# OrangePi_Zero2.net
KiCad netlist of a schematic drawn in Altium Designer
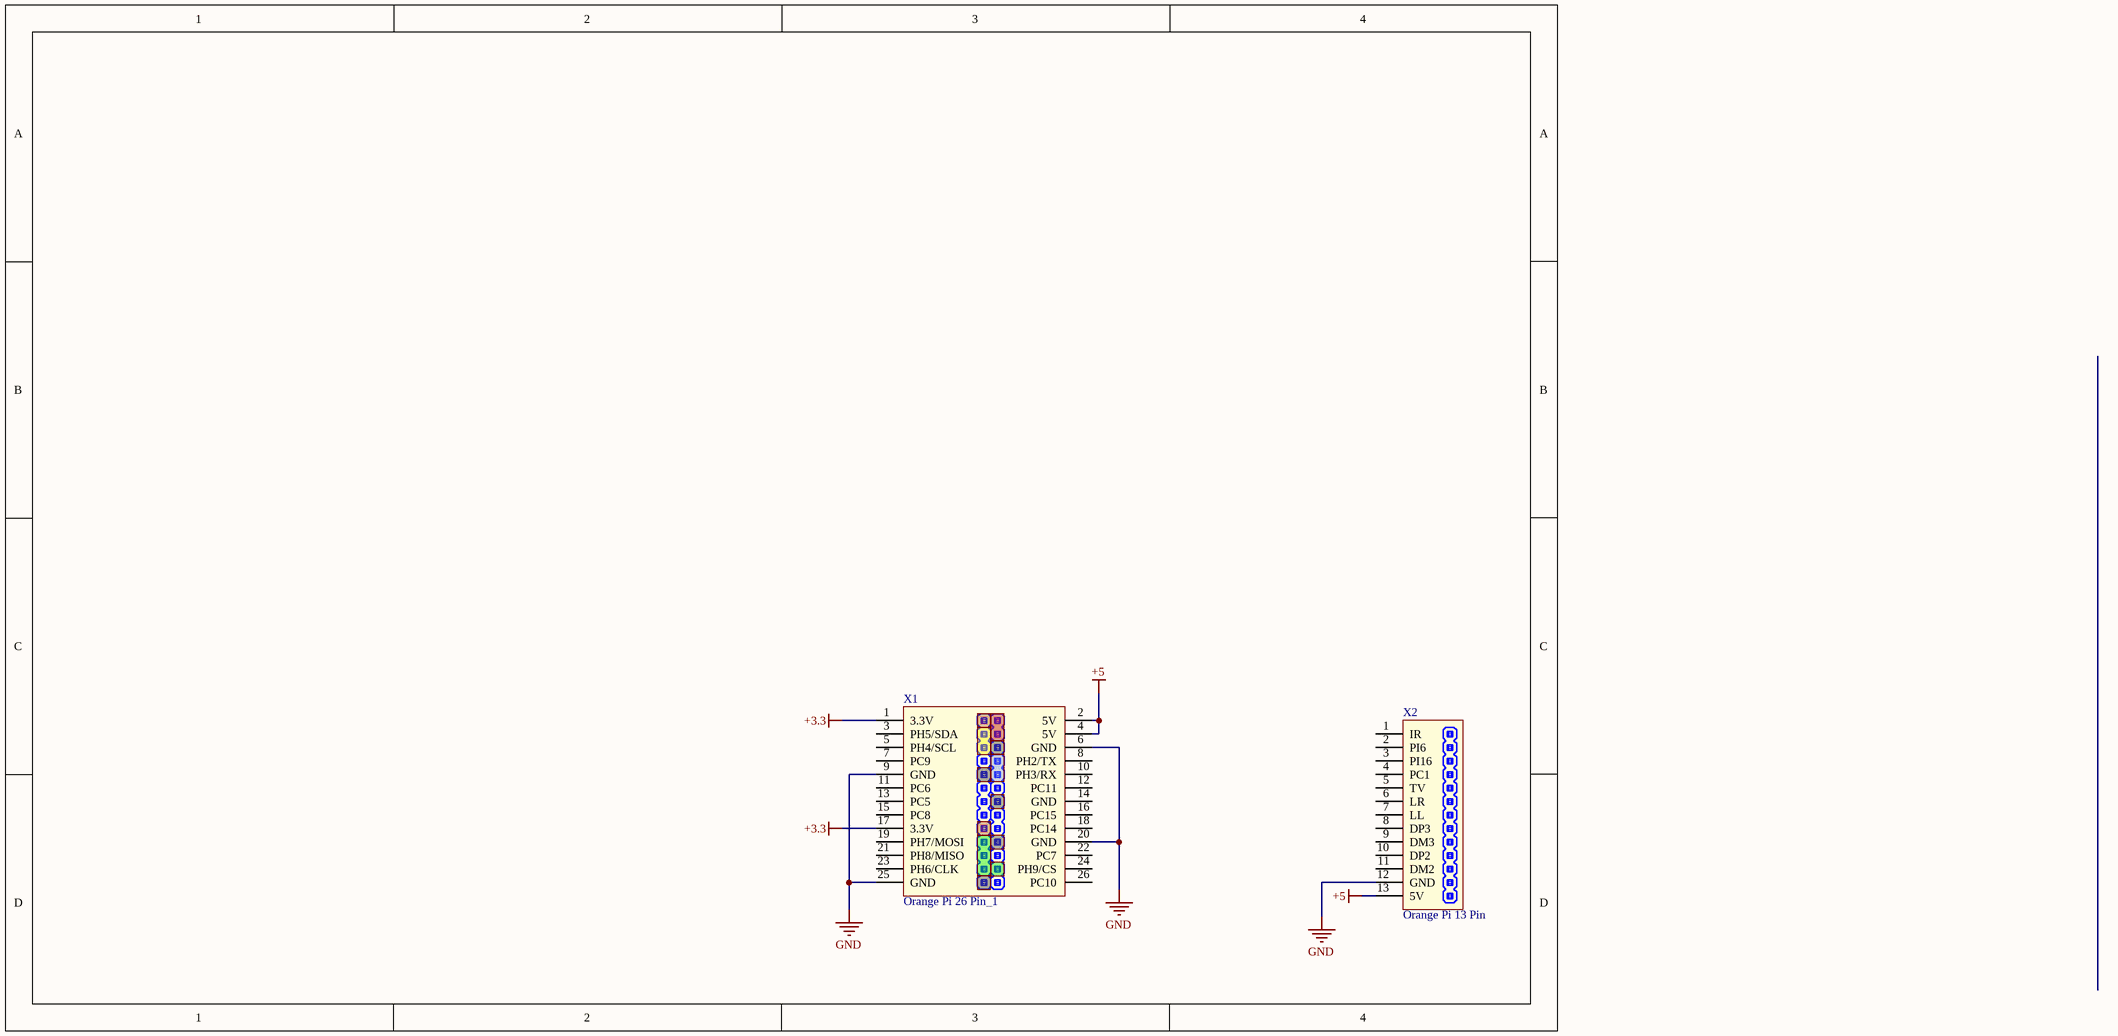
[diagram p0: OrangePi_Zero2.SchDoc]

(export (version "E")
  (design (tool "Eeschema 10.0.6"))
  (components
    (comp (ref "X1")
      (value "Orange Pi 26 Pin_1")
      (footprint "26pin Orange Pi Bottom")
      (libsource (lib "oneBoardComputers") (part "Orange Pi 26 Pin_1"))
    )
    (comp (ref "X2")
      (value "Orange Pi 13 Pin")
      (footprint "13pin Orange Pi")
      (libsource (lib "oneBoardComputers") (part "Orange Pi 13 Pin"))
    )
  )
  (nets
    (net (code "1") (name "+3.3") (class "Default")
      (node (ref "X1") (pin "1") (pinfunction "3.3V_1") (pintype "passive"))
      (node (ref "X1") (pin "17") (pinfunction "3.3V_17") (pintype "passive"))
    )
    (net (code "2") (name "+5") (class "Default")
      (node (ref "X1") (pin "2") (pinfunction "5V_2") (pintype "passive"))
      (node (ref "X1") (pin "4") (pinfunction "5V_4") (pintype "passive"))
      (node (ref "X2") (pin "13") (pinfunction "5V_13") (pintype "passive"))
    )
    (net (code "3") (name "GND") (class "Default")
      (node (ref "X1") (pin "20") (pinfunction "GND_20") (pintype "passive"))
      (node (ref "X1") (pin "25") (pinfunction "GND_25") (pintype "passive"))
      (node (ref "X1") (pin "6") (pinfunction "GND_6") (pintype "passive"))
      (node (ref "X1") (pin "9") (pinfunction "GND_9") (pintype "passive"))
      (node (ref "X2") (pin "12") (pinfunction "GND_12") (pintype "passive"))
    )
    (net (code "4") (name "unconnected-(X1-GND-Pad14)") (class "Default")
      (node (ref "X1") (pin "14") (pinfunction "GND_14") (pintype "passive"))
    )
    (net (code "5") (name "unconnected-(X1-PC5-Pad13)") (class "Default")
      (node (ref "X1") (pin "13") (pinfunction "PC5_13") (pintype "passive"))
    )
    (net (code "6") (name "unconnected-(X1-PC6-Pad11)") (class "Default")
      (node (ref "X1") (pin "11") (pinfunction "PC6_11") (pintype "passive"))
    )
    (net (code "7") (name "unconnected-(X1-PC7-Pad22)") (class "Default")
      (node (ref "X1") (pin "22") (pinfunction "PC7_22") (pintype "passive"))
    )
    (net (code "8") (name "unconnected-(X1-PC8-Pad15)") (class "Default")
      (node (ref "X1") (pin "15") (pinfunction "PC8_15") (pintype "passive"))
    )
    (net (code "9") (name "unconnected-(X1-PC9-Pad7)") (class "Default")
      (node (ref "X1") (pin "7") (pinfunction "PC9_7") (pintype "passive"))
    )
    (net (code "10") (name "unconnected-(X1-PC10-Pad26)") (class "Default")
      (node (ref "X1") (pin "26") (pinfunction "PC10_26") (pintype "passive"))
    )
    (net (code "11") (name "unconnected-(X1-PC11-Pad12)") (class "Default")
      (node (ref "X1") (pin "12") (pinfunction "PC11_12") (pintype "passive"))
    )
    (net (code "12") (name "unconnected-(X1-PC14-Pad18)") (class "Default")
      (node (ref "X1") (pin "18") (pinfunction "PC14_18") (pintype "passive"))
    )
    (net (code "13") (name "unconnected-(X1-PC15-Pad16)") (class "Default")
      (node (ref "X1") (pin "16") (pinfunction "PC15_16") (pintype "passive"))
    )
    (net (code "14") (name "unconnected-(X1-PH2{slash}TX-Pad8)") (class "Default")
      (node (ref "X1") (pin "8") (pinfunction "PH2/TX_8") (pintype "passive"))
    )
    (net (code "15") (name "unconnected-(X1-PH3{slash}RX-Pad10)") (class "Default")
      (node (ref "X1") (pin "10") (pinfunction "PH3/RX_10") (pintype "passive"))
    )
    (net (code "16") (name "unconnected-(X1-PH4{slash}SCL-Pad5)") (class "Default")
      (node (ref "X1") (pin "5") (pinfunction "PH4/SCL_5") (pintype "passive"))
    )
    (net (code "17") (name "unconnected-(X1-PH5{slash}SDA-Pad3)") (class "Default")
      (node (ref "X1") (pin "3") (pinfunction "PH5/SDA_3") (pintype "passive"))
    )
    (net (code "18") (name "unconnected-(X1-PH6{slash}CLK-Pad23)") (class "Default")
      (node (ref "X1") (pin "23") (pinfunction "PH6/CLK_23") (pintype "passive"))
    )
    (net (code "19") (name "unconnected-(X1-PH7{slash}MOSI-Pad19)") (class "Default")
      (node (ref "X1") (pin "19") (pinfunction "PH7/MOSI_19") (pintype "passive"))
    )
    (net (code "20") (name "unconnected-(X1-PH8{slash}MISO-Pad21)") (class "Default")
      (node (ref "X1") (pin "21") (pinfunction "PH8/MISO_21") (pintype "passive"))
    )
    (net (code "21") (name "unconnected-(X1-PH9{slash}CS-Pad24)") (class "Default")
      (node (ref "X1") (pin "24") (pinfunction "PH9/CS_24") (pintype "passive"))
    )
    (net (code "22") (name "unconnected-(X2-DM2-Pad11)") (class "Default")
      (node (ref "X2") (pin "11") (pinfunction "DM2_11") (pintype "passive"))
    )
    (net (code "23") (name "unconnected-(X2-DM3-Pad9)") (class "Default")
      (node (ref "X2") (pin "9") (pinfunction "DM3_9") (pintype "passive"))
    )
    (net (code "24") (name "unconnected-(X2-DP2-Pad10)") (class "Default")
      (node (ref "X2") (pin "10") (pinfunction "DP2_10") (pintype "passive"))
    )
    (net (code "25") (name "unconnected-(X2-DP3-Pad8)") (class "Default")
      (node (ref "X2") (pin "8") (pinfunction "DP3_8") (pintype "passive"))
    )
    (net (code "26") (name "unconnected-(X2-IR-Pad1)") (class "Default")
      (node (ref "X2") (pin "1") (pinfunction "IR_1") (pintype "passive"))
    )
    (net (code "27") (name "unconnected-(X2-LL-Pad7)") (class "Default")
      (node (ref "X2") (pin "7") (pinfunction "LL_7") (pintype "passive"))
    )
    (net (code "28") (name "unconnected-(X2-LR-Pad6)") (class "Default")
      (node (ref "X2") (pin "6") (pinfunction "LR_6") (pintype "passive"))
    )
    (net (code "29") (name "unconnected-(X2-PC1-Pad4)") (class "Default")
      (node (ref "X2") (pin "4") (pinfunction "PC1_4") (pintype "passive"))
    )
    (net (code "30") (name "unconnected-(X2-PI6-Pad2)") (class "Default")
      (node (ref "X2") (pin "2") (pinfunction "PI6_2") (pintype "passive"))
    )
    (net (code "31") (name "unconnected-(X2-PI16-Pad3)") (class "Default")
      (node (ref "X2") (pin "3") (pinfunction "PI16_3") (pintype "passive"))
    )
    (net (code "32") (name "unconnected-(X2-TV-Pad5)") (class "Default")
      (node (ref "X2") (pin "5") (pinfunction "TV_5") (pintype "passive"))
    )
  )
)
